# Hammerhead_-_LPC4337_MCU_R1_1.net
KiCad netlist of a schematic drawn in Altium Designer
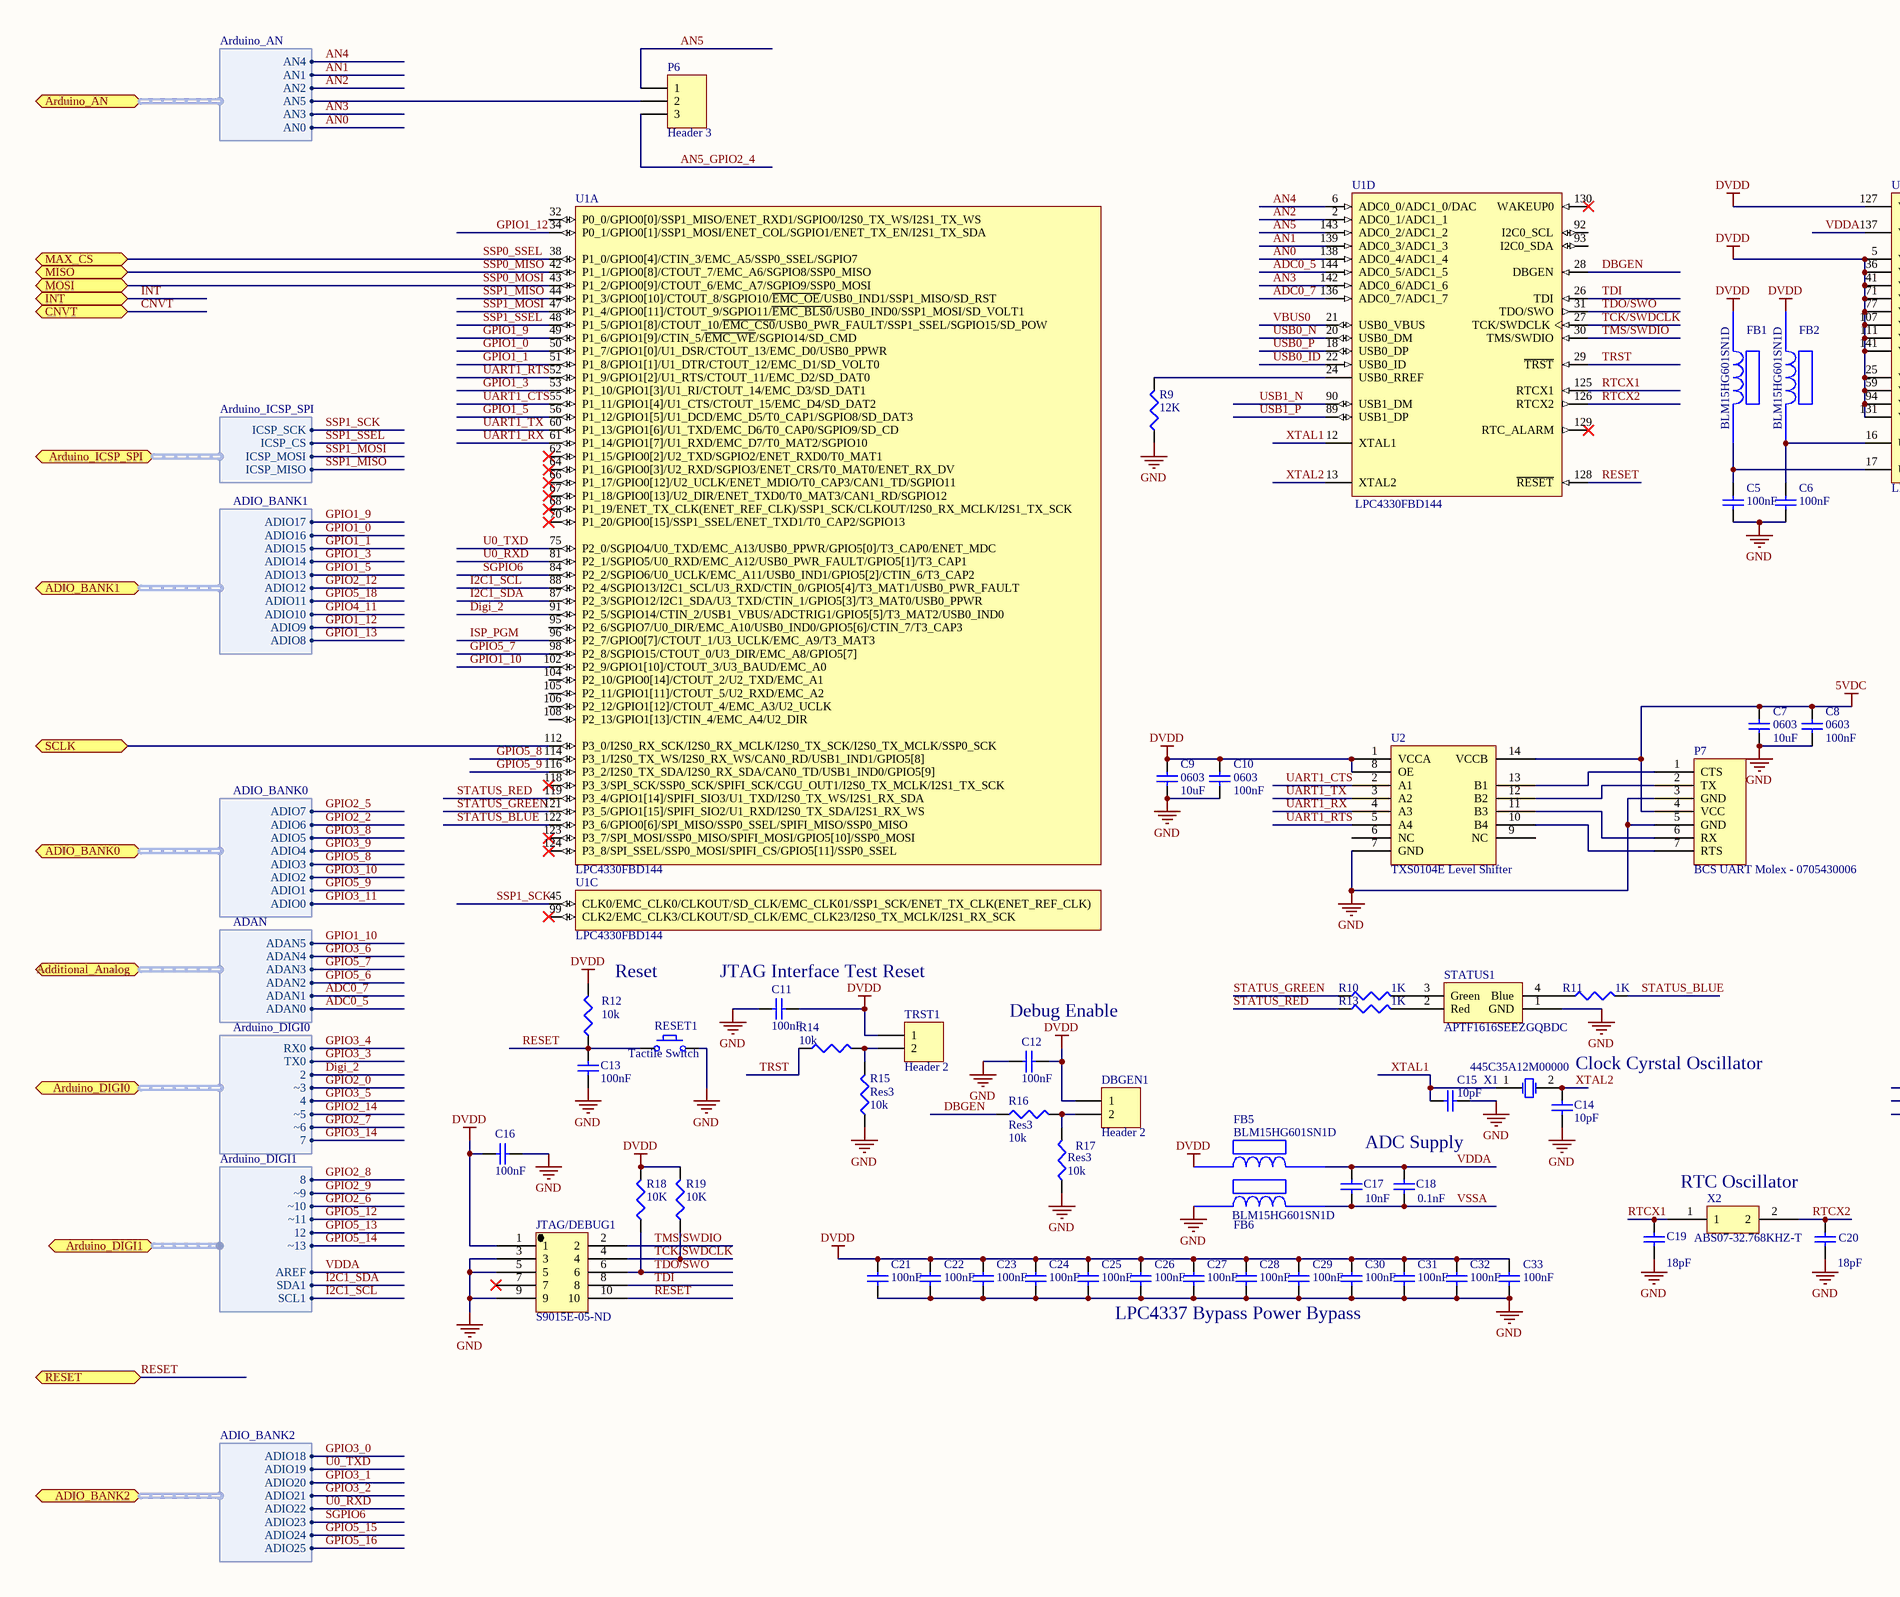
[diagram p0: Hammerhead - LPC4337 MCU R1.1.SchDoc, left]
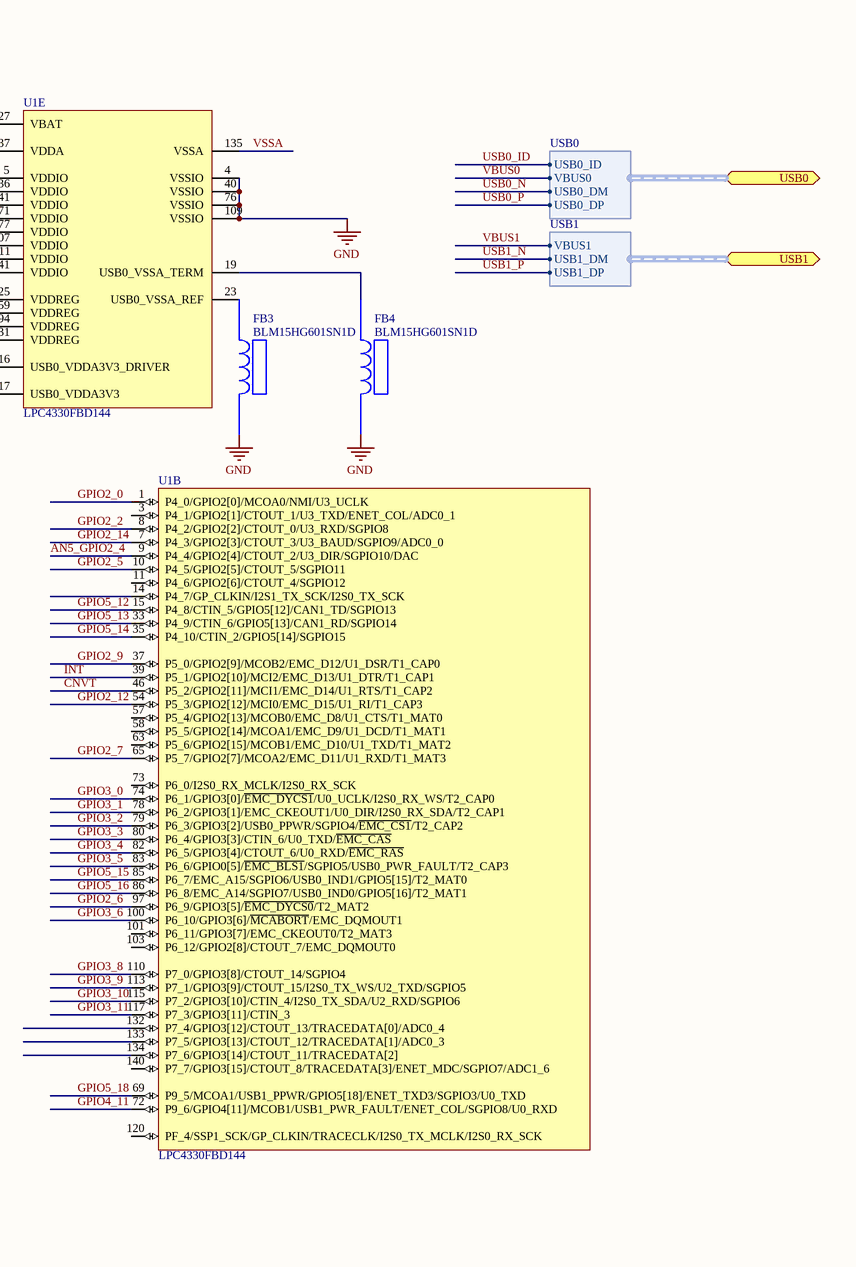
[diagram p1: Hammerhead - LPC4337 MCU R1.1.SchDoc, right]

(export (version "E")
  (design (tool "Eeschema 10.0.6"))
  (components
    (comp (ref "C5")
      (value "100nF")
      (footprint "1608[0603]")
      (description "Capacitor (Semiconductor SIM Model)")
      (fields (field (name "Comment") "Cap Semi") (field (name "PUBLISHER") "Altium Limited"))
      (libsource (lib "Miscellaneous Devices") (part "Cap Semi"))
    )
    (comp (ref "C6")
      (value "100nF")
      (footprint "1608[0603]")
      (description "Capacitor (Semiconductor SIM Model)")
      (fields (field (name "Comment") "Cap Semi") (field (name "PUBLISHER") "Altium Limited"))
      (libsource (lib "Miscellaneous Devices") (part "Cap Semi"))
    )
    (comp (ref "C7")
      (value "0603")
      (footprint "1608[0603]")
      (description "Capacitor (Semiconductor SIM Model)")
      (fields (field (name "ALTIUM_VALUE") "10uF") (field (name "PUBLISHER") "Altium Limited"))
      (libsource (lib "Miscellaneous Devices") (part "Cap Semi"))
    )
    (comp (ref "C8")
      (value "0603")
      (footprint "1608[0603]")
      (description "Capacitor (Semiconductor SIM Model)")
      (fields (field (name "ALTIUM_VALUE") "100nF") (field (name "PUBLISHER") "Altium Limited"))
      (libsource (lib "Miscellaneous Devices") (part "Cap Semi"))
    )
    (comp (ref "C9")
      (value "0603")
      (footprint "1608[0603]")
      (description "Capacitor (Semiconductor SIM Model)")
      (fields (field (name "ALTIUM_VALUE") "10uF") (field (name "PUBLISHER") "Altium Limited"))
      (libsource (lib "Miscellaneous Devices") (part "Cap Semi"))
    )
    (comp (ref "C10")
      (value "0603")
      (footprint "1608[0603]")
      (description "Capacitor (Semiconductor SIM Model)")
      (fields (field (name "ALTIUM_VALUE") "100nF") (field (name "PUBLISHER") "Altium Limited"))
      (libsource (lib "Miscellaneous Devices") (part "Cap Semi"))
    )
    (comp (ref "C11")
      (value "100nF")
      (footprint "1608[0603]")
      (description "Capacitor (Semiconductor SIM Model)")
      (fields (field (name "Comment") "Cap Semi") (field (name "PUBLISHER") "Altium Limited"))
      (libsource (lib "Miscellaneous Devices") (part "Cap Semi"))
    )
    (comp (ref "C12")
      (value "100nF")
      (footprint "1608[0603]")
      (description "Capacitor (Semiconductor SIM Model)")
      (fields (field (name "Comment") "Cap Semi") (field (name "PUBLISHER") "Altium Limited"))
      (libsource (lib "Miscellaneous Devices") (part "Cap Semi"))
    )
    (comp (ref "C13")
      (value "100nF")
      (footprint "1608[0603]")
      (description "Capacitor (Semiconductor SIM Model)")
      (fields (field (name "Comment") "Cap Semi") (field (name "PUBLISHER") "Altium Limited"))
      (libsource (lib "Miscellaneous Devices") (part "Cap Semi"))
    )
    (comp (ref "C14")
      (value "10pF")
      (footprint "1608[0603]")
      (description "Capacitor (Semiconductor SIM Model)")
      (fields (field (name "Comment") "Cap Semi") (field (name "PUBLISHER") "Altium Limited"))
      (libsource (lib "Miscellaneous Devices") (part "Cap Semi"))
    )
    (comp (ref "C15")
      (value "10pF")
      (footprint "1608[0603]")
      (description "Capacitor (Semiconductor SIM Model)")
      (fields (field (name "Comment") "Cap Semi") (field (name "PUBLISHER") "Altium Limited"))
      (libsource (lib "Miscellaneous Devices") (part "Cap Semi"))
    )
    (comp (ref "C16")
      (value "100nF")
      (footprint "1608[0603]")
      (description "Capacitor (Semiconductor SIM Model)")
      (fields (field (name "Comment") "Cap Semi") (field (name "PUBLISHER") "Altium Limited"))
      (libsource (lib "Miscellaneous Devices") (part "Cap Semi"))
    )
    (comp (ref "C17")
      (value "10nF")
      (footprint "1608[0603]")
      (description "Capacitor (Semiconductor SIM Model)")
      (fields (field (name "Comment") "Cap Semi") (field (name "PUBLISHER") "Altium Limited"))
      (libsource (lib "Miscellaneous Devices") (part "Cap Semi"))
    )
    (comp (ref "C18")
      (value "0.1nF")
      (footprint "1608[0603]")
      (description "Capacitor (Semiconductor SIM Model)")
      (fields (field (name "Comment") "Cap Semi") (field (name "PUBLISHER") "Altium Limited"))
      (libsource (lib "Miscellaneous Devices") (part "Cap Semi"))
    )
    (comp (ref "C19")
      (value "18pF")
      (footprint "1608[0603]")
      (description "Capacitor (Semiconductor SIM Model)")
      (fields (field (name "Comment") "Cap Semi") (field (name "PUBLISHER") "Altium Limited"))
      (libsource (lib "Miscellaneous Devices") (part "Cap Semi"))
    )
    (comp (ref "C20")
      (value "18pF")
      (footprint "1608[0603]")
      (description "Capacitor (Semiconductor SIM Model)")
      (fields (field (name "Comment") "Cap Semi") (field (name "PUBLISHER") "Altium Limited"))
      (libsource (lib "Miscellaneous Devices") (part "Cap Semi"))
    )
    (comp (ref "C21")
      (value "100nF")
      (footprint "1608[0603]")
      (description "Capacitor (Semiconductor SIM Model)")
      (fields (field (name "Comment") "Cap Semi") (field (name "PUBLISHER") "Altium Limited"))
      (libsource (lib "Miscellaneous Devices") (part "Cap Semi"))
    )
    (comp (ref "C22")
      (value "100nF")
      (footprint "1608[0603]")
      (description "Capacitor (Semiconductor SIM Model)")
      (fields (field (name "Comment") "Cap Semi") (field (name "PUBLISHER") "Altium Limited"))
      (libsource (lib "Miscellaneous Devices") (part "Cap Semi"))
    )
    (comp (ref "C23")
      (value "100nF")
      (footprint "1608[0603]")
      (description "Capacitor (Semiconductor SIM Model)")
      (fields (field (name "Comment") "Cap Semi") (field (name "PUBLISHER") "Altium Limited"))
      (libsource (lib "Miscellaneous Devices") (part "Cap Semi"))
    )
    (comp (ref "C24")
      (value "100nF")
      (footprint "1608[0603]")
      (description "Capacitor (Semiconductor SIM Model)")
      (fields (field (name "Comment") "Cap Semi") (field (name "PUBLISHER") "Altium Limited"))
      (libsource (lib "Miscellaneous Devices") (part "Cap Semi"))
    )
    (comp (ref "C25")
      (value "100nF")
      (footprint "1608[0603]")
      (description "Capacitor (Semiconductor SIM Model)")
      (fields (field (name "Comment") "Cap Semi") (field (name "PUBLISHER") "Altium Limited"))
      (libsource (lib "Miscellaneous Devices") (part "Cap Semi"))
    )
    (comp (ref "C26")
      (value "100nF")
      (footprint "1608[0603]")
      (description "Capacitor (Semiconductor SIM Model)")
      (fields (field (name "Comment") "Cap Semi") (field (name "PUBLISHER") "Altium Limited"))
      (libsource (lib "Miscellaneous Devices") (part "Cap Semi"))
    )
    (comp (ref "C27")
      (value "100nF")
      (footprint "1608[0603]")
      (description "Capacitor (Semiconductor SIM Model)")
      (fields (field (name "Comment") "Cap Semi") (field (name "PUBLISHER") "Altium Limited"))
      (libsource (lib "Miscellaneous Devices") (part "Cap Semi"))
    )
    (comp (ref "C28")
      (value "100nF")
      (footprint "1608[0603]")
      (description "Capacitor (Semiconductor SIM Model)")
      (fields (field (name "Comment") "Cap Semi") (field (name "PUBLISHER") "Altium Limited"))
      (libsource (lib "Miscellaneous Devices") (part "Cap Semi"))
    )
    (comp (ref "C29")
      (value "100nF")
      (footprint "1608[0603]")
      (description "Capacitor (Semiconductor SIM Model)")
      (fields (field (name "Comment") "Cap Semi") (field (name "PUBLISHER") "Altium Limited"))
      (libsource (lib "Miscellaneous Devices") (part "Cap Semi"))
    )
    (comp (ref "C30")
      (value "100nF")
      (footprint "1608[0603]")
      (description "Capacitor (Semiconductor SIM Model)")
      (fields (field (name "Comment") "Cap Semi") (field (name "PUBLISHER") "Altium Limited"))
      (libsource (lib "Miscellaneous Devices") (part "Cap Semi"))
    )
    (comp (ref "C31")
      (value "100nF")
      (footprint "1608[0603]")
      (description "Capacitor (Semiconductor SIM Model)")
      (fields (field (name "Comment") "Cap Semi") (field (name "PUBLISHER") "Altium Limited"))
      (libsource (lib "Miscellaneous Devices") (part "Cap Semi"))
    )
    (comp (ref "C32")
      (value "100nF")
      (footprint "1608[0603]")
      (description "Capacitor (Semiconductor SIM Model)")
      (fields (field (name "Comment") "Cap Semi") (field (name "PUBLISHER") "Altium Limited"))
      (libsource (lib "Miscellaneous Devices") (part "Cap Semi"))
    )
    (comp (ref "C33")
      (value "100nF")
      (footprint "1608[0603]")
      (description "Capacitor (Semiconductor SIM Model)")
      (fields (field (name "Comment") "Cap Semi") (field (name "PUBLISHER") "Altium Limited"))
      (libsource (lib "Miscellaneous Devices") (part "Cap Semi"))
    )
    (comp (ref "DBGEN1")
      (value "Header 2")
      (footprint "HDR1X2")
      (description "Header, 2-Pin")
      (fields (field (name "PUBLISHER") "Altium Limited"))
      (libsource (lib "Miscellaneous Connectors") (part "Header 2"))
    )
    (comp (ref "FB1")
      (value "BLM15HG601SN1D")
      (footprint "BLM18PG121SN1D")
      (libsource (lib "AHD Part Library") (part "BLM15HG601SN1D"))
    )
    (comp (ref "FB2")
      (value "BLM15HG601SN1D")
      (footprint "BLM18PG121SN1D")
      (libsource (lib "AHD Part Library") (part "BLM15HG601SN1D"))
    )
    (comp (ref "FB3")
      (value "BLM15HG601SN1D")
      (footprint "BLM18PG121SN1D")
      (libsource (lib "AHD Part Library") (part "BLM15HG601SN1D"))
    )
    (comp (ref "FB4")
      (value "BLM15HG601SN1D")
      (footprint "BLM18PG121SN1D")
      (libsource (lib "AHD Part Library") (part "BLM15HG601SN1D"))
    )
    (comp (ref "FB5")
      (value "BLM15HG601SN1D")
      (footprint "BLM18PG121SN1D")
      (libsource (lib "AHD Part Library") (part "BLM15HG601SN1D"))
    )
    (comp (ref "FB6")
      (value "BLM15HG601SN1D")
      (footprint "BLM18PG121SN1D")
      (libsource (lib "AHD Part Library") (part "BLM15HG601SN1D"))
    )
    (comp (ref "JTAG/DEBUG1")
      (value "S9015E-05-ND")
      (footprint "S9015E-05-ND")
      (libsource (lib "AHD Part Library") (part "S9015E-05-ND"))
    )
    (comp (ref "P6")
      (value "Header 3")
      (footprint "HDR1X3")
      (description "Header, 3-Pin")
      (fields (field (name "PUBLISHER") "Altium Limited"))
      (libsource (lib "Miscellaneous Connectors") (part "Header 3"))
    )
    (comp (ref "P7")
      (value "BCS UART Molex - 0705430006")
      (footprint "BCS Serial Port - Molex")
      (description "BCS UART Port Molex")
      (libsource (lib "SunIO Schematic Symbol Lib") (part "BCS Serial Port - Molex"))
    )
    (comp (ref "R9")
      (value "12K")
      (footprint "J1-0603")
      (description "Resistor")
      (fields (field (name "Comment") "Res3") (field (name "PUBLISHER") "Altium Limited"))
      (libsource (lib "Miscellaneous Devices") (part "Res3"))
    )
    (comp (ref "R10")
      (value "1K")
      (footprint "J1-0603")
      (description "Resistor")
      (fields (field (name "Comment") "Res3") (field (name "PUBLISHER") "Altium Limited"))
      (libsource (lib "Miscellaneous Devices") (part "Res3"))
    )
    (comp (ref "R11")
      (value "1K")
      (footprint "J1-0603")
      (description "Resistor")
      (fields (field (name "Comment") "Res3") (field (name "PUBLISHER") "Altium Limited"))
      (libsource (lib "Miscellaneous Devices") (part "Res3"))
    )
    (comp (ref "R12")
      (value "10k")
      (footprint "J1-0603")
      (description "Resistor")
      (fields (field (name "Comment") "Res3") (field (name "PUBLISHER") "Altium Limited"))
      (libsource (lib "Miscellaneous Devices") (part "Res3"))
    )
    (comp (ref "R13")
      (value "1K")
      (footprint "J1-0603")
      (description "Resistor")
      (fields (field (name "Comment") "Res3") (field (name "PUBLISHER") "Altium Limited"))
      (libsource (lib "Miscellaneous Devices") (part "Res3"))
    )
    (comp (ref "R14")
      (value "10k")
      (footprint "J1-0603")
      (description "Resistor")
      (fields (field (name "Comment") "Res3") (field (name "PUBLISHER") "Altium Limited"))
      (libsource (lib "Miscellaneous Devices") (part "Res3"))
    )
    (comp (ref "R15")
      (value "Res3")
      (footprint "J1-0603")
      (description "Resistor")
      (fields (field (name "ALTIUM_VALUE") "10k") (field (name "PUBLISHER") "Altium Limited"))
      (libsource (lib "Miscellaneous Devices") (part "Res3"))
    )
    (comp (ref "R16")
      (value "Res3")
      (footprint "J1-0603")
      (description "Resistor")
      (fields (field (name "ALTIUM_VALUE") "10k") (field (name "PUBLISHER") "Altium Limited"))
      (libsource (lib "Miscellaneous Devices") (part "Res3"))
    )
    (comp (ref "R17")
      (value "Res3")
      (footprint "J1-0603")
      (description "Resistor")
      (fields (field (name "ALTIUM_VALUE") "10k") (field (name "PUBLISHER") "Altium Limited"))
      (libsource (lib "Miscellaneous Devices") (part "Res3"))
    )
    (comp (ref "R18")
      (value "10K")
      (footprint "J1-0603")
      (description "Resistor")
      (fields (field (name "Comment") "Res3") (field (name "PUBLISHER") "Altium Limited"))
      (libsource (lib "Miscellaneous Devices") (part "Res3"))
    )
    (comp (ref "R19")
      (value "10K")
      (footprint "J1-0603")
      (description "Resistor")
      (fields (field (name "Comment") "Res3") (field (name "PUBLISHER") "Altium Limited"))
      (libsource (lib "Miscellaneous Devices") (part "Res3"))
    )
    (comp (ref "RESET1")
      (value "Tactile Switch")
      (footprint "TL3301")
      (libsource (lib "Adams Altium Library") (part "Tactile Switch"))
    )
    (comp (ref "STATUS1")
      (value "APTF1616SEEZGQBDC")
      (footprint "RGB LED APTF1616SEEZGQBDC")
      (description "RGB LED")
      (libsource (lib "Adams Altium Library") (part "RGB LED APTF1616SEEZGQBDC"))
    )
    (comp (ref "TRST1")
      (value "Header 2")
      (footprint "HDR1X2")
      (description "Header, 2-Pin")
      (fields (field (name "PUBLISHER") "Altium Limited"))
      (libsource (lib "Miscellaneous Connectors") (part "Header 2"))
    )
    (comp (ref "U1")
      (value "LPC4330FBD144")
      (footprint "SOT486-1_V")
      (libsource (lib "NXP Semiconductors Cortex-M4") (part "LPC4330FBD144"))
    )
    (comp (ref "U2")
      (value "TXS0104E Level Shifter")
      (footprint "RGY  (S-PVQFN-N14)")
      (description "TXS0104E - Bidriectional Opendrain/pushpull level shift")
      (libsource (lib "SunIO Schematic Symbol Lib") (part "TXS0104E"))
    )
    (comp (ref "X1")
      (value "445C35A12M00000")
      (footprint "445C35A12M00000")
      (description "Crystal Oscillator")
      (fields (field (name "PUBLISHER") "Altium Limited"))
      (libsource (lib "Miscellaneous Devices") (part "XTAL"))
    )
    (comp (ref "X2")
      (value "ABS07-32.768KHZ-T")
      (footprint "ABS07-32.768KHZ-T")
      (description "ABS07-32.768KHZ-T RTC Crystal Oscillator")
      (libsource (lib "AHD Part Library") (part "ABS07-32.768KHZ-T"))
    )
  )
  (nets
    (net (code "11") (name "/ADC0_5") (class "Default")
      (node (ref "U1") (pin "144") (pinfunction "ADC0_5/ADC1_5_144") (pintype "input"))
    )
    (net (code "12") (name "/ADC0_7") (class "Default")
      (node (ref "U1") (pin "136") (pinfunction "ADC0_7/ADC1_7_136") (pintype "input"))
    )
    (net (code "13") (name "/AN0") (class "Default")
      (node (ref "U1") (pin "138") (pinfunction "ADC0_4/ADC1_4_138") (pintype "input"))
    )
    (net (code "14") (name "/AN1") (class "Default")
      (node (ref "U1") (pin "139") (pinfunction "ADC0_3/ADC1_3_139") (pintype "input"))
    )
    (net (code "15") (name "/AN2") (class "Default")
      (node (ref "U1") (pin "2") (pinfunction "ADC0_1/ADC1_1_2") (pintype "input"))
    )
    (net (code "16") (name "/AN3") (class "Default")
      (node (ref "U1") (pin "142") (pinfunction "ADC0_6/ADC1_6_142") (pintype "input"))
    )
    (net (code "17") (name "/AN4") (class "Default")
      (node (ref "U1") (pin "6") (pinfunction "ADC0_0/ADC1_0/DAC_6") (pintype "input"))
    )
    (net (code "18") (name "/AN5") (class "Default")
      (node (ref "P6") (pin "1") (pinfunction "1_1") (pintype "passive"))
      (node (ref "U1") (pin "143") (pinfunction "ADC0_2/ADC1_2_143") (pintype "input"))
    )
    (net (code "19") (name "/AN5_GPIO2_4") (class "Default")
      (node (ref "P6") (pin "3") (pinfunction "3_3") (pintype "passive"))
      (node (ref "U1") (pin "9") (pinfunction "P4_4/GPIO2[4]/CTOUT_2/U3_DIR/SGPIO10/DAC_9") (pintype "bidirectional"))
    )
    (net (code "20") (name "/CNVT") (class "Default")
      (node (ref "U1") (pin "46") (pinfunction "P5_2/GPIO2[11]/MCI1/EMC_D14/U1_RTS/T1_CAP2_46") (pintype "bidirectional"))
    )
    (net (code "21") (name "/DBGEN") (class "Default")
      (node (ref "R16") (pin "1") (pinfunction "1_1") (pintype "passive"))
      (node (ref "U1") (pin "28") (pinfunction "DBGEN_28") (pintype "input"))
    )
    (net (code "22") (name "/Digi_2") (class "Default")
      (node (ref "U1") (pin "91") (pinfunction "P2_5/SGPIO14/CTIN_2/USB1_VBUS/ADCTRIG1/GPIO5[5]/T3_MAT2/USB0_IND0_91") (pintype "bidirectional"))
    )
    (net (code "23") (name "/GPIO1_0") (class "Default")
      (node (ref "U1") (pin "50") (pinfunction "P1_7/GPIO1[0]/U1_DSR/CTOUT_13/EMC_D0/USB0_PPWR_50") (pintype "bidirectional"))
    )
    (net (code "24") (name "/GPIO1_1") (class "Default")
      (node (ref "U1") (pin "51") (pinfunction "P1_8/GPIO1[1]/U1_DTR/CTOUT_12/EMC_D1/SD_VOLT0_51") (pintype "bidirectional"))
    )
    (net (code "25") (name "/GPIO1_3") (class "Default")
      (node (ref "U1") (pin "53") (pinfunction "P1_10/GPIO1[3]/U1_RI/CTOUT_14/EMC_D3/SD_DAT1_53") (pintype "bidirectional"))
    )
    (net (code "26") (name "/GPIO1_5") (class "Default")
      (node (ref "U1") (pin "56") (pinfunction "P1_12/GPIO1[5]/U1_DCD/EMC_D5/T0_CAP1/SGPIO8/SD_DAT3_56") (pintype "bidirectional"))
    )
    (net (code "27") (name "/GPIO1_9") (class "Default")
      (node (ref "U1") (pin "49") (pinfunction "P1_6/GPIO1[9]/CTIN_5/~{EMC_WE}/SGPIO14/SD_CMD_49") (pintype "bidirectional"))
    )
    (net (code "28") (name "/GPIO1_10") (class "Default")
      (node (ref "U1") (pin "102") (pinfunction "P2_9/GPIO1[10]/CTOUT_3/U3_BAUD/EMC_A0_102") (pintype "bidirectional"))
    )
    (net (code "29") (name "/GPIO1_12") (class "Default")
      (node (ref "U1") (pin "34") (pinfunction "P0_1/GPIO0[1]/SSP1_MOSI/ENET_COL/SGPIO1/ENET_TX_EN/I2S1_TX_SDA_34") (pintype "bidirectional"))
    )
    (net (code "31") (name "/GPIO2_0") (class "Default")
      (node (ref "U1") (pin "1") (pinfunction "P4_0/GPIO2[0]/MCOA0/NMI/U3_UCLK_1") (pintype "bidirectional"))
    )
    (net (code "32") (name "/GPIO2_2") (class "Default")
      (node (ref "U1") (pin "8") (pinfunction "P4_2/GPIO2[2]/CTOUT_0/U3_RXD/SGPIO8_8") (pintype "bidirectional"))
    )
    (net (code "33") (name "/GPIO2_5") (class "Default")
      (node (ref "U1") (pin "10") (pinfunction "P4_5/GPIO2[5]/CTOUT_5/SGPIO11_10") (pintype "bidirectional"))
    )
    (net (code "34") (name "/GPIO2_6") (class "Default")
      (node (ref "U1") (pin "97") (pinfunction "P6_9/GPIO3[5]/~{EMC_DYCS0}/T2_MAT2_97") (pintype "bidirectional"))
    )
    (net (code "35") (name "/GPIO2_7") (class "Default")
      (node (ref "U1") (pin "65") (pinfunction "P5_7/GPIO2[7]/MCOA2/EMC_D11/U1_RXD/T1_MAT3_65") (pintype "bidirectional"))
    )
    (net (code "37") (name "/GPIO2_9") (class "Default")
      (node (ref "U1") (pin "37") (pinfunction "P5_0/GPIO2[9]/MCOB2/EMC_D12/U1_DSR/T1_CAP0_37") (pintype "bidirectional"))
    )
    (net (code "38") (name "/GPIO2_12") (class "Default")
      (node (ref "U1") (pin "54") (pinfunction "P5_3/GPIO2[12]/MCI0/EMC_D15/U1_RI/T1_CAP3_54") (pintype "bidirectional"))
    )
    (net (code "39") (name "/GPIO2_14") (class "Default")
      (node (ref "U1") (pin "7") (pinfunction "P4_3/GPIO2[3]/CTOUT_3/U3_BAUD/SGPIO9/ADC0_0_7") (pintype "bidirectional"))
    )
    (net (code "40") (name "/GPIO3_0") (class "Default")
      (node (ref "U1") (pin "74") (pinfunction "P6_1/GPIO3[0]/~{EMC_DYCS1}/U0_UCLK/I2S0_RX_WS/T2_CAP0_74") (pintype "bidirectional"))
    )
    (net (code "41") (name "/GPIO3_1") (class "Default")
      (node (ref "U1") (pin "78") (pinfunction "P6_2/GPIO3[1]/EMC_CKEOUT1/U0_DIR/I2S0_RX_SDA/T2_CAP1_78") (pintype "bidirectional"))
    )
    (net (code "42") (name "/GPIO3_2") (class "Default")
      (node (ref "U1") (pin "79") (pinfunction "P6_3/GPIO3[2]/USB0_PPWR/SGPIO4/~{EMC_CS1}/T2_CAP2_79") (pintype "bidirectional"))
    )
    (net (code "43") (name "/GPIO3_3") (class "Default")
      (node (ref "U1") (pin "80") (pinfunction "P6_4/GPIO3[3]/CTIN_6/U0_TXD/~{EMC_CAS}_80") (pintype "bidirectional"))
    )
    (net (code "44") (name "/GPIO3_4") (class "Default")
      (node (ref "U1") (pin "82") (pinfunction "P6_5/GPIO3[4]/CTOUT_6/U0_RXD/~{EMC_RAS}_82") (pintype "bidirectional"))
    )
    (net (code "45") (name "/GPIO3_5") (class "Default")
      (node (ref "U1") (pin "83") (pinfunction "P6_6/GPIO0[5]/~{EMC_BLS1}/SGPIO5/USB0_PWR_FAULT/T2_CAP3_83") (pintype "bidirectional"))
    )
    (net (code "46") (name "/GPIO3_6") (class "Default")
      (node (ref "U1") (pin "100") (pinfunction "P6_10/GPIO3[6]/~{MCABORT}/EMC_DQMOUT1_100") (pintype "bidirectional"))
    )
    (net (code "47") (name "/GPIO3_8") (class "Default")
      (node (ref "U1") (pin "110") (pinfunction "P7_0/GPIO3[8]/CTOUT_14/SGPIO4_110") (pintype "bidirectional"))
    )
    (net (code "48") (name "/GPIO3_9") (class "Default")
      (node (ref "U1") (pin "113") (pinfunction "P7_1/GPIO3[9]/CTOUT_15/I2S0_TX_WS/U2_TXD/SGPIO5_113") (pintype "bidirectional"))
    )
    (net (code "49") (name "/GPIO3_10") (class "Default")
      (node (ref "U1") (pin "115") (pinfunction "P7_2/GPIO3[10]/CTIN_4/I2S0_TX_SDA/U2_RXD/SGPIO6_115") (pintype "bidirectional"))
    )
    (net (code "50") (name "/GPIO3_11") (class "Default")
      (node (ref "U1") (pin "117") (pinfunction "P7_3/GPIO3[11]/CTIN_3_117") (pintype "bidirectional"))
    )
    (net (code "52") (name "/GPIO4_11") (class "Default")
      (node (ref "U1") (pin "72") (pinfunction "P9_6/GPIO4[11]/MCOB1/USB1_PWR_FAULT/ENET_COL/SGPIO8/U0_RXD_72") (pintype "bidirectional"))
    )
    (net (code "54") (name "/GPIO5_7") (class "Default")
      (node (ref "U1") (pin "98") (pinfunction "P2_8/SGPIO15/CTOUT_0/U3_DIR/EMC_A8/GPIO5[7]_98") (pintype "bidirectional"))
    )
    (net (code "55") (name "/GPIO5_8") (class "Default")
      (node (ref "U1") (pin "114") (pinfunction "P3_1/I2S0_TX_WS/I2S0_RX_WS/CAN0_RD/USB1_IND1/GPIO5[8]_114") (pintype "bidirectional"))
    )
    (net (code "56") (name "/GPIO5_9") (class "Default")
      (node (ref "U1") (pin "116") (pinfunction "P3_2/I2S0_TX_SDA/I2S0_RX_SDA/CAN0_TD/USB1_IND0/GPIO5[9]_116") (pintype "bidirectional"))
    )
    (net (code "57") (name "/GPIO5_12") (class "Default")
      (node (ref "U1") (pin "15") (pinfunction "P4_8/CTIN_5/GPIO5[12]/CAN1_TD/SGPIO13_15") (pintype "bidirectional"))
    )
    (net (code "58") (name "/GPIO5_13") (class "Default")
      (node (ref "U1") (pin "33") (pinfunction "P4_9/CTIN_6/GPIO5[13]/CAN1_RD/SGPIO14_33") (pintype "bidirectional"))
    )
    (net (code "59") (name "/GPIO5_14") (class "Default")
      (node (ref "U1") (pin "35") (pinfunction "P4_10/CTIN_2/GPIO5[14]/SGPIO15_35") (pintype "bidirectional"))
    )
    (net (code "60") (name "/GPIO5_15") (class "Default")
      (node (ref "U1") (pin "85") (pinfunction "P6_7/EMC_A15/SGPIO6/USB0_IND1/GPIO5[15]/T2_MAT0_85") (pintype "bidirectional"))
    )
    (net (code "61") (name "/GPIO5_16") (class "Default")
      (node (ref "U1") (pin "86") (pinfunction "P6_8/EMC_A14/SGPIO7/USB0_IND0/GPIO5[16]/T2_MAT1_86") (pintype "bidirectional"))
    )
    (net (code "62") (name "/GPIO5_18") (class "Default")
      (node (ref "U1") (pin "69") (pinfunction "P9_5/MCOA1/USB1_PPWR/GPIO5[18]/ENET_TXD3/SGPIO3/U0_TXD_69") (pintype "bidirectional"))
    )
    (net (code "63") (name "/I2C1_SCL") (class "Default")
      (node (ref "U1") (pin "88") (pinfunction "P2_4/SGPIO13/I2C1_SCL/U3_RXD/CTIN_0/GPIO5[4]/T3_MAT1/USB0_PWR_FAULT_88") (pintype "bidirectional"))
    )
    (net (code "64") (name "/I2C1_SDA") (class "Default")
      (node (ref "U1") (pin "87") (pinfunction "P2_3/SGPIO12/I2C1_SDA/U3_TXD/CTIN_1/GPIO5[3]/T3_MAT0/USB0_PPWR_87") (pintype "bidirectional"))
    )
    (net (code "65") (name "/INT") (class "Default")
      (node (ref "U1") (pin "39") (pinfunction "P5_1/GPIO2[10]/MCI2/EMC_D13/U1_DTR/T1_CAP1_39") (pintype "bidirectional"))
    )
    (net (code "66") (name "/ISP_PGM") (class "Default")
      (node (ref "U1") (pin "96") (pinfunction "P2_7/GPIO0[7]/CTOUT_1/U3_UCLK/EMC_A9/T3_MAT3_96") (pintype "bidirectional"))
    )
    (net (code "67") (name "/RESET") (class "Default")
      (node (ref "C13") (pin "2") (pinfunction "2_2") (pintype "passive"))
      (node (ref "JTAG/DEBUG1") (pin "10") (pinfunction "10_10") (pintype "passive"))
      (node (ref "R12") (pin "1") (pinfunction "1_1") (pintype "passive"))
      (node (ref "RESET1") (pin "1") (pintype "passive"))
      (node (ref "U1") (pin "128") (pinfunction "~{RESET}_128") (pintype "input"))
    )
    (net (code "68") (name "/RTCX1") (class "Default")
      (node (ref "C19") (pin "2") (pinfunction "2_2") (pintype "passive"))
      (node (ref "U1") (pin "125") (pinfunction "RTCX1_125") (pintype "input"))
      (node (ref "X2") (pin "1") (pinfunction "1_1") (pintype "passive"))
    )
    (net (code "69") (name "/RTCX2") (class "Default")
      (node (ref "C20") (pin "2") (pinfunction "2_2") (pintype "passive"))
      (node (ref "U1") (pin "126") (pinfunction "RTCX2_126") (pintype "output"))
      (node (ref "X2") (pin "2") (pinfunction "2_2") (pintype "passive"))
    )
    (net (code "70") (name "/SCLK") (class "Default")
      (node (ref "U1") (pin "112") (pinfunction "P3_0/I2S0_RX_SCK/I2S0_RX_MCLK/I2S0_TX_SCK/I2S0_TX_MCLK/SSP0_SCK_112") (pintype "bidirectional"))
    )
    (net (code "71") (name "/SGPIO6") (class "Default")
      (node (ref "U1") (pin "84") (pinfunction "P2_2/SGPIO6/U0_UCLK/EMC_A11/USB0_IND1/GPIO5[2]/CTIN_6/T3_CAP2_84") (pintype "bidirectional"))
    )
    (net (code "72") (name "/SSP0_MISO") (class "Default")
      (node (ref "U1") (pin "42") (pinfunction "P1_1/GPIO0[8]/CTOUT_7/EMC_A6/SGPIO8/SSP0_MISO_42") (pintype "bidirectional"))
    )
    (net (code "73") (name "/SSP0_MOSI") (class "Default")
      (node (ref "U1") (pin "43") (pinfunction "P1_2/GPIO0[9]/CTOUT_6/EMC_A7/SGPIO9/SSP0_MOSI_43") (pintype "bidirectional"))
    )
    (net (code "74") (name "/SSP0_SSEL") (class "Default")
      (node (ref "U1") (pin "38") (pinfunction "P1_0/GPIO0[4]/CTIN_3/EMC_A5/SSP0_SSEL/SGPIO7_38") (pintype "bidirectional"))
    )
    (net (code "75") (name "/SSP1_MISO") (class "Default")
      (node (ref "U1") (pin "44") (pinfunction "P1_3/GPIO0[10]/CTOUT_8/SGPIO10/~{EMC_OE}/USB0_IND1/SSP1_MISO/SD_RST_44") (pintype "bidirectional"))
    )
    (net (code "76") (name "/SSP1_MOSI") (class "Default")
      (node (ref "U1") (pin "47") (pinfunction "P1_4/GPIO0[11]/CTOUT_9/SGPIO11/~{EMC_BLS0}/USB0_IND0/SSP1_MOSI/SD_VOLT1_47") (pintype "bidirectional"))
    )
    (net (code "77") (name "/SSP1_SCK") (class "Default")
      (node (ref "U1") (pin "45") (pinfunction "CLK0/EMC_CLK0/CLKOUT/SD_CLK/EMC_CLK01/SSP1_SCK/ENET_TX_CLK(ENET_REF_CLK)_45") (pintype "bidirectional"))
    )
    (net (code "78") (name "/SSP1_SSEL") (class "Default")
      (node (ref "U1") (pin "48") (pinfunction "P1_5/GPIO1[8]/CTOUT_10/~{EMC_CS0}/USB0_PWR_FAULT/SSP1_SSEL/SGPIO15/SD_POW_48") (pintype "bidirectional"))
    )
    (net (code "79") (name "/STATUS_BLUE") (class "Default")
      (node (ref "R11") (pin "2") (pinfunction "2_2") (pintype "passive"))
      (node (ref "U1") (pin "122") (pinfunction "P3_6/GPIO0[6]/SPI_MISO/SSP0_SSEL/SPIFI_MISO/SSP0_MISO_122") (pintype "bidirectional"))
    )
    (net (code "80") (name "/STATUS_GREEN") (class "Default")
      (node (ref "R10") (pin "1") (pinfunction "1_1") (pintype "passive"))
      (node (ref "U1") (pin "121") (pinfunction "P3_5/GPIO1[15]/SPIFI_SIO2/U1_RXD/I2S0_TX_SDA/I2S1_RX_WS_121") (pintype "bidirectional"))
    )
    (net (code "81") (name "/STATUS_RED") (class "Default")
      (node (ref "R13") (pin "1") (pinfunction "1_1") (pintype "passive"))
      (node (ref "U1") (pin "119") (pinfunction "P3_4/GPIO1[14]/SPIFI_SIO3/U1_TXD/I2S0_TX_WS/I2S1_RX_SDA_119") (pintype "bidirectional"))
    )
    (net (code "82") (name "/TCK{slash}SWDCLK") (class "Default")
      (node (ref "JTAG/DEBUG1") (pin "4") (pinfunction "4_4") (pintype "passive"))
      (node (ref "R19") (pin "1") (pinfunction "1_1") (pintype "passive"))
      (node (ref "U1") (pin "27") (pinfunction "TCK/SWDCLK_27") (pintype "input"))
    )
    (net (code "83") (name "/TDI") (class "Default")
      (node (ref "JTAG/DEBUG1") (pin "8") (pinfunction "8_8") (pintype "passive"))
      (node (ref "U1") (pin "26") (pinfunction "TDI_26") (pintype "input"))
    )
    (net (code "84") (name "/TDO{slash}SWO") (class "Default")
      (node (ref "JTAG/DEBUG1") (pin "6") (pinfunction "6_6") (pintype "passive"))
      (node (ref "R18") (pin "1") (pinfunction "1_1") (pintype "passive"))
      (node (ref "U1") (pin "31") (pinfunction "TDO/SWO_31") (pintype "output"))
    )
    (net (code "85") (name "/TMS{slash}SWDIO") (class "Default")
      (node (ref "JTAG/DEBUG1") (pin "2") (pinfunction "2_2") (pintype "passive"))
      (node (ref "U1") (pin "30") (pinfunction "TMS/SWDIO_30") (pintype "input"))
    )
    (net (code "86") (name "/TRST") (class "Default")
      (node (ref "R14") (pin "1") (pinfunction "1_1") (pintype "passive"))
      (node (ref "U1") (pin "29") (pinfunction "~{TRST}_29") (pintype "input"))
    )
    (net (code "87") (name "/U0_RXD") (class "Default")
      (node (ref "U1") (pin "81") (pinfunction "P2_1/SGPIO5/U0_RXD/EMC_A12/USB0_PWR_FAULT/GPIO5[1]/T3_CAP1_81") (pintype "bidirectional"))
    )
    (net (code "88") (name "/U0_TXD") (class "Default")
      (node (ref "U1") (pin "75") (pinfunction "P2_0/SGPIO4/U0_TXD/EMC_A13/USB0_PPWR/GPIO5[0]/T3_CAP0/ENET_MDC_75") (pintype "bidirectional"))
    )
    (net (code "89") (name "/UART1_CTS") (class "Default")
      (node (ref "U1") (pin "55") (pinfunction "P1_11/GPIO1[4]/U1_CTS/CTOUT_15/EMC_D4/SD_DAT2_55") (pintype "bidirectional"))
      (node (ref "U2") (pin "2") (pinfunction "A1_2") (pintype "passive"))
    )
    (net (code "90") (name "/UART1_RTS") (class "Default")
      (node (ref "U1") (pin "52") (pinfunction "P1_9/GPIO1[2]/U1_RTS/CTOUT_11/EMC_D2/SD_DAT0_52") (pintype "bidirectional"))
      (node (ref "U2") (pin "5") (pinfunction "A4_5") (pintype "passive"))
    )
    (net (code "91") (name "/UART1_RX") (class "Default")
      (node (ref "U1") (pin "61") (pinfunction "P1_14/GPIO1[7]/U1_RXD/EMC_D7/T0_MAT2/SGPIO10_61") (pintype "bidirectional"))
      (node (ref "U2") (pin "4") (pinfunction "A3_4") (pintype "passive"))
    )
    (net (code "92") (name "/UART1_TX") (class "Default")
      (node (ref "U1") (pin "60") (pinfunction "P1_13/GPIO1[6]/U1_TXD/EMC_D6/T0_CAP0/SGPIO9/SD_CD_60") (pintype "bidirectional"))
      (node (ref "U2") (pin "3") (pinfunction "A2_3") (pintype "passive"))
    )
    (net (code "93") (name "/USB0_ID") (class "Default")
      (node (ref "U1") (pin "22") (pinfunction "USB0_ID_22") (pintype "input"))
    )
    (net (code "94") (name "/USB0_N") (class "Default")
      (node (ref "U1") (pin "20") (pinfunction "USB0_DM_20") (pintype "bidirectional"))
    )
    (net (code "95") (name "/USB0_P") (class "Default")
      (node (ref "U1") (pin "18") (pinfunction "USB0_DP_18") (pintype "bidirectional"))
    )
    (net (code "96") (name "/USB1_N") (class "Default")
      (node (ref "U1") (pin "90") (pinfunction "USB1_DM_90") (pintype "bidirectional"))
    )
    (net (code "97") (name "/USB1_P") (class "Default")
      (node (ref "U1") (pin "89") (pinfunction "USB1_DP_89") (pintype "bidirectional"))
    )
    (net (code "98") (name "/VBUS0") (class "Default")
      (node (ref "U1") (pin "21") (pinfunction "USB0_VBUS_21") (pintype "bidirectional"))
    )
    (net (code "100") (name "/VDDA") (class "Default")
      (node (ref "C17") (pin "2") (pinfunction "2_2") (pintype "passive"))
      (node (ref "C18") (pin "2") (pinfunction "2_2") (pintype "passive"))
      (node (ref "FB5") (pin "2") (pinfunction "2_2") (pintype "passive"))
      (node (ref "U1") (pin "137") (pinfunction "VDDA_137") (pintype "power_in"))
    )
    (net (code "101") (name "/VSSA") (class "Default")
      (node (ref "C17") (pin "1") (pinfunction "1_1") (pintype "passive"))
      (node (ref "C18") (pin "1") (pinfunction "1_1") (pintype "passive"))
      (node (ref "FB6") (pin "2") (pinfunction "2_2") (pintype "passive"))
      (node (ref "U1") (pin "135") (pinfunction "VSSA_135") (pintype "power_in"))
    )
    (net (code "102") (name "/XTAL1") (class "Default")
      (node (ref "C15") (pin "2") (pinfunction "2_2") (pintype "passive"))
      (node (ref "U1") (pin "12") (pinfunction "XTAL1_12") (pintype "passive"))
      (node (ref "X1") (pin "1") (pinfunction "OSC1_1") (pintype "passive"))
    )
    (net (code "103") (name "/XTAL2") (class "Default")
      (node (ref "C14") (pin "2") (pinfunction "2_2") (pintype "passive"))
      (node (ref "U1") (pin "13") (pinfunction "XTAL2_13") (pintype "passive"))
      (node (ref "X1") (pin "2") (pinfunction "OSC2_2") (pintype "passive"))
    )
    (net (code "114") (name "5VDC") (class "Default")
      (node (ref "C7") (pin "2") (pinfunction "2_2") (pintype "passive"))
      (node (ref "C8") (pin "2") (pinfunction "2_2") (pintype "passive"))
      (node (ref "P7") (pin "4") (pinfunction "VCC_4") (pintype "passive"))
      (node (ref "U2") (pin "14") (pinfunction "VCCB_14") (pintype "passive"))
    )
    (net (code "115") (name "DVDD") (class "Default")
      (node (ref "C10") (pin "2") (pinfunction "2_2") (pintype "passive"))
      (node (ref "C11") (pin "2") (pinfunction "2_2") (pintype "passive"))
      (node (ref "C12") (pin "2") (pinfunction "2_2") (pintype "passive"))
      (node (ref "C16") (pin "1") (pinfunction "1_1") (pintype "passive"))
      (node (ref "C21") (pin "2") (pinfunction "2_2") (pintype "passive"))
      (node (ref "C22") (pin "2") (pinfunction "2_2") (pintype "passive"))
      (node (ref "C23") (pin "2") (pinfunction "2_2") (pintype "passive"))
      (node (ref "C24") (pin "2") (pinfunction "2_2") (pintype "passive"))
      (node (ref "C25") (pin "2") (pinfunction "2_2") (pintype "passive"))
      (node (ref "C26") (pin "2") (pinfunction "2_2") (pintype "passive"))
      (node (ref "C27") (pin "2") (pinfunction "2_2") (pintype "passive"))
      (node (ref "C28") (pin "2") (pinfunction "2_2") (pintype "passive"))
      (node (ref "C29") (pin "2") (pinfunction "2_2") (pintype "passive"))
      (node (ref "C30") (pin "2") (pinfunction "2_2") (pintype "passive"))
      (node (ref "C31") (pin "2") (pinfunction "2_2") (pintype "passive"))
      (node (ref "C32") (pin "2") (pinfunction "2_2") (pintype "passive"))
      (node (ref "C33") (pin "2") (pinfunction "2_2") (pintype "passive"))
      (node (ref "C9") (pin "2") (pinfunction "2_2") (pintype "passive"))
      (node (ref "DBGEN1") (pin "1") (pinfunction "1_1") (pintype "passive"))
      (node (ref "FB1") (pin "1") (pinfunction "1_1") (pintype "passive"))
      (node (ref "FB2") (pin "1") (pinfunction "1_1") (pintype "passive"))
      (node (ref "FB5") (pin "1") (pinfunction "1_1") (pintype "passive"))
      (node (ref "JTAG/DEBUG1") (pin "1") (pinfunction "1_1") (pintype "passive"))
      (node (ref "R12") (pin "2") (pinfunction "2_2") (pintype "passive"))
      (node (ref "R18") (pin "2") (pinfunction "2_2") (pintype "passive"))
      (node (ref "R19") (pin "2") (pinfunction "2_2") (pintype "passive"))
      (node (ref "TRST1") (pin "1") (pinfunction "1_1") (pintype "passive"))
      (node (ref "U1") (pin "107") (pinfunction "VDDIO_107") (pintype "power_in"))
      (node (ref "U1") (pin "111") (pinfunction "VDDIO_111") (pintype "power_in"))
      (node (ref "U1") (pin "127") (pinfunction "VBAT_127") (pintype "power_in"))
      (node (ref "U1") (pin "131") (pinfunction "VDDREG_131") (pintype "power_in"))
      (node (ref "U1") (pin "141") (pinfunction "VDDIO_141") (pintype "power_in"))
      (node (ref "U1") (pin "25") (pinfunction "VDDREG_25") (pintype "power_in"))
      (node (ref "U1") (pin "36") (pinfunction "VDDIO_36") (pintype "power_in"))
      (node (ref "U1") (pin "41") (pinfunction "VDDIO_41") (pintype "power_in"))
      (node (ref "U1") (pin "5") (pinfunction "VDDIO_5") (pintype "power_in"))
      (node (ref "U1") (pin "59") (pinfunction "VDDREG_59") (pintype "power_in"))
      (node (ref "U1") (pin "71") (pinfunction "VDDIO_71") (pintype "power_in"))
      (node (ref "U1") (pin "77") (pinfunction "VDDIO_77") (pintype "power_in"))
      (node (ref "U1") (pin "94") (pinfunction "VDDREG_94") (pintype "power_in"))
      (node (ref "U2") (pin "1") (pinfunction "VCCA_1") (pintype "passive"))
      (node (ref "U2") (pin "8") (pinfunction "OE_8") (pintype "passive"))
    )
    (net (code "116") (name "GND") (class "Default")
      (node (ref "C10") (pin "1") (pinfunction "1_1") (pintype "passive"))
      (node (ref "C11") (pin "1") (pinfunction "1_1") (pintype "passive"))
      (node (ref "C12") (pin "1") (pinfunction "1_1") (pintype "passive"))
      (node (ref "C13") (pin "1") (pinfunction "1_1") (pintype "passive"))
      (node (ref "C14") (pin "1") (pinfunction "1_1") (pintype "passive"))
      (node (ref "C15") (pin "1") (pinfunction "1_1") (pintype "passive"))
      (node (ref "C16") (pin "2") (pinfunction "2_2") (pintype "passive"))
      (node (ref "C19") (pin "1") (pinfunction "1_1") (pintype "passive"))
      (node (ref "C20") (pin "1") (pinfunction "1_1") (pintype "passive"))
      (node (ref "C21") (pin "1") (pinfunction "1_1") (pintype "passive"))
      (node (ref "C22") (pin "1") (pinfunction "1_1") (pintype "passive"))
      (node (ref "C23") (pin "1") (pinfunction "1_1") (pintype "passive"))
      (node (ref "C24") (pin "1") (pinfunction "1_1") (pintype "passive"))
      (node (ref "C25") (pin "1") (pinfunction "1_1") (pintype "passive"))
      (node (ref "C26") (pin "1") (pinfunction "1_1") (pintype "passive"))
      (node (ref "C27") (pin "1") (pinfunction "1_1") (pintype "passive"))
      (node (ref "C28") (pin "1") (pinfunction "1_1") (pintype "passive"))
      (node (ref "C29") (pin "1") (pinfunction "1_1") (pintype "passive"))
      (node (ref "C30") (pin "1") (pinfunction "1_1") (pintype "passive"))
      (node (ref "C31") (pin "1") (pinfunction "1_1") (pintype "passive"))
      (node (ref "C32") (pin "1") (pinfunction "1_1") (pintype "passive"))
      (node (ref "C33") (pin "1") (pinfunction "1_1") (pintype "passive"))
      (node (ref "C5") (pin "1") (pinfunction "1_1") (pintype "passive"))
      (node (ref "C6") (pin "1") (pinfunction "1_1") (pintype "passive"))
      (node (ref "C7") (pin "1") (pinfunction "1_1") (pintype "passive"))
      (node (ref "C8") (pin "1") (pinfunction "1_1") (pintype "passive"))
      (node (ref "C9") (pin "1") (pinfunction "1_1") (pintype "passive"))
      (node (ref "FB3") (pin "2") (pinfunction "2_2") (pintype "passive"))
      (node (ref "FB4") (pin "2") (pinfunction "2_2") (pintype "passive"))
      (node (ref "FB6") (pin "1") (pinfunction "1_1") (pintype "passive"))
      (node (ref "JTAG/DEBUG1") (pin "3") (pinfunction "3_3") (pintype "passive"))
      (node (ref "JTAG/DEBUG1") (pin "5") (pinfunction "5_5") (pintype "passive"))
      (node (ref "JTAG/DEBUG1") (pin "9") (pinfunction "9_9") (pintype "passive"))
      (node (ref "P7") (pin "3") (pinfunction "GND_3") (pintype "passive"))
      (node (ref "P7") (pin "5") (pinfunction "GND_5") (pintype "passive"))
      (node (ref "R15") (pin "1") (pinfunction "1_1") (pintype "passive"))
      (node (ref "R17") (pin "1") (pinfunction "1_1") (pintype "passive"))
      (node (ref "R9") (pin "1") (pinfunction "1_1") (pintype "passive"))
      (node (ref "RESET1") (pin "2") (pintype "passive"))
      (node (ref "STATUS1") (pin "1") (pinfunction "GND_1") (pintype "passive"))
      (node (ref "U1") (pin "109") (pinfunction "VSSIO_109") (pintype "power_in"))
      (node (ref "U1") (pin "4") (pinfunction "VSSIO_4") (pintype "power_in"))
      (node (ref "U1") (pin "40") (pinfunction "VSSIO_40") (pintype "power_in"))
      (node (ref "U1") (pin "76") (pinfunction "VSSIO_76") (pintype "power_in"))
      (node (ref "U2") (pin "7") (pinfunction "GND_7") (pintype "passive"))
    )
    (net (code "117") (name "Net-(DBGEN1-Pad2)") (class "Default")
      (node (ref "DBGEN1") (pin "2") (pinfunction "2_2") (pintype "passive"))
      (node (ref "R16") (pin "2") (pinfunction "2_2") (pintype "passive"))
      (node (ref "R17") (pin "2") (pinfunction "2_2") (pintype "passive"))
    )
    (net (code "118") (name "Net-(P7-CTS)") (class "Default")
      (node (ref "P7") (pin "1") (pinfunction "CTS_1") (pintype "passive"))
      (node (ref "U2") (pin "13") (pinfunction "B1_13") (pintype "passive"))
    )
    (net (code "119") (name "Net-(P7-RTS)") (class "Default")
      (node (ref "P7") (pin "7") (pinfunction "RTS_7") (pintype "passive"))
      (node (ref "U2") (pin "10") (pinfunction "B4_10") (pintype "passive"))
    )
    (net (code "120") (name "Net-(P7-RX)") (class "Default")
      (node (ref "P7") (pin "6") (pinfunction "RX_6") (pintype "passive"))
      (node (ref "U2") (pin "11") (pinfunction "B3_11") (pintype "passive"))
    )
    (net (code "121") (name "Net-(P7-TX)") (class "Default")
      (node (ref "P7") (pin "2") (pinfunction "TX_2") (pintype "passive"))
      (node (ref "U2") (pin "12") (pinfunction "B2_12") (pintype "passive"))
    )
    (net (code "122") (name "Net-(R14-Pad2)") (class "Default")
      (node (ref "R14") (pin "2") (pinfunction "2_2") (pintype "passive"))
      (node (ref "R15") (pin "2") (pinfunction "2_2") (pintype "passive"))
      (node (ref "TRST1") (pin "2") (pinfunction "2_2") (pintype "passive"))
    )
    (net (code "123") (name "Net-(STATUS1-Blue)") (class "Default")
      (node (ref "R11") (pin "1") (pinfunction "1_1") (pintype "passive"))
      (node (ref "STATUS1") (pin "4") (pinfunction "Blue_4") (pintype "passive"))
    )
    (net (code "124") (name "Net-(STATUS1-Green)") (class "Default")
      (node (ref "R10") (pin "2") (pinfunction "2_2") (pintype "passive"))
      (node (ref "STATUS1") (pin "3") (pinfunction "Green_3") (pintype "passive"))
    )
    (net (code "125") (name "Net-(STATUS1-Red)") (class "Default")
      (node (ref "R13") (pin "2") (pinfunction "2_2") (pintype "passive"))
      (node (ref "STATUS1") (pin "2") (pinfunction "Red_2") (pintype "passive"))
    )
    (net (code "126") (name "Net-(U1D-USB0_RREF)") (class "Default")
      (node (ref "R9") (pin "2") (pinfunction "2_2") (pintype "passive"))
      (node (ref "U1") (pin "24") (pinfunction "USB0_RREF_24") (pintype "passive"))
    )
    (net (code "127") (name "Net-(U1E-USB0_VDDA3V3)") (class "Default")
      (node (ref "C5") (pin "2") (pinfunction "2_2") (pintype "passive"))
      (node (ref "FB1") (pin "2") (pinfunction "2_2") (pintype "passive"))
      (node (ref "U1") (pin "17") (pinfunction "USB0_VDDA3V3_17") (pintype "power_in"))
    )
    (net (code "128") (name "Net-(U1E-USB0_VDDA3V3_DRIVER)") (class "Default")
      (node (ref "C6") (pin "2") (pinfunction "2_2") (pintype "passive"))
      (node (ref "FB2") (pin "2") (pinfunction "2_2") (pintype "passive"))
      (node (ref "U1") (pin "16") (pinfunction "USB0_VDDA3V3_DRIVER_16") (pintype "power_in"))
    )
    (net (code "129") (name "Net-(U1E-USB0_VSSA_REF)") (class "Default")
      (node (ref "FB3") (pin "1") (pinfunction "1_1") (pintype "passive"))
      (node (ref "U1") (pin "23") (pinfunction "USB0_VSSA_REF_23") (pintype "power_in"))
    )
    (net (code "130") (name "Net-(U1E-USB0_VSSA_TERM)") (class "Default")
      (node (ref "FB4") (pin "1") (pinfunction "1_1") (pintype "passive"))
      (node (ref "U1") (pin "19") (pinfunction "USB0_VSSA_TERM_19") (pintype "power_in"))
    )
    (net (code "131") (name "unconnected-(JTAG/DEBUG1-Pad7)") (class "Default")
      (node (ref "JTAG/DEBUG1") (pin "7") (pinfunction "7_7") (pintype "passive+no_connect"))
    )
    (net (code "132") (name "unconnected-(P6-Pad2)") (class "Default")
      (node (ref "P6") (pin "2") (pinfunction "2_2") (pintype "passive"))
    )
    (net (code "133") (name "unconnected-(U1A-P0_0{slash}GPIO0[0]{slash}SSP1_MISO{slash}ENET_RXD1{slash}SGPIO0{slash}I2S0_TX_WS{slash}I2S1_TX_WS-Pad32)") (class "Default")
      (node (ref "U1") (pin "32") (pinfunction "P0_0/GPIO0[0]/SSP1_MISO/ENET_RXD1/SGPIO0/I2S0_TX_WS/I2S1_TX_WS_32") (pintype "bidirectional"))
    )
    (net (code "134") (name "unconnected-(U1A-P1_15{slash}GPIO0[2]{slash}U2_TXD{slash}SGPIO2{slash}ENET_RXD0{slash}T0_MAT1-Pad62)") (class "Default")
      (node (ref "U1") (pin "62") (pinfunction "P1_15/GPIO0[2]/U2_TXD/SGPIO2/ENET_RXD0/T0_MAT1_62") (pintype "bidirectional+no_connect"))
    )
    (net (code "135") (name "unconnected-(U1A-P1_16{slash}GPIO0[3]{slash}U2_RXD{slash}SGPIO3{slash}ENET_CRS{slash}T0_MAT0{slash}ENET_RX_DV-Pad64)") (class "Default")
      (node (ref "U1") (pin "64") (pinfunction "P1_16/GPIO0[3]/U2_RXD/SGPIO3/ENET_CRS/T0_MAT0/ENET_RX_DV_64") (pintype "bidirectional+no_connect"))
    )
    (net (code "136") (name "unconnected-(U1A-P1_17{slash}GPIO0[12]{slash}U2_UCLK{slash}ENET_MDIO{slash}T0_CAP3{slash}CAN1_TD{slash}SGPIO11-Pad66)") (class "Default")
      (node (ref "U1") (pin "66") (pinfunction "P1_17/GPIO0[12]/U2_UCLK/ENET_MDIO/T0_CAP3/CAN1_TD/SGPIO11_66") (pintype "bidirectional+no_connect"))
    )
    (net (code "137") (name "unconnected-(U1A-P1_18{slash}GPIO0[13]{slash}U2_DIR{slash}ENET_TXD0{slash}T0_MAT3{slash}CAN1_RD{slash}SGPIO12-Pad67)") (class "Default")
      (node (ref "U1") (pin "67") (pinfunction "P1_18/GPIO0[13]/U2_DIR/ENET_TXD0/T0_MAT3/CAN1_RD/SGPIO12_67") (pintype "bidirectional+no_connect"))
    )
    (net (code "138") (name "unconnected-(U1A-P1_19{slash}ENET_TX_CLK(ENET_REF_CLK){slash}SSP1_SCK{slash}CLKOUT{slash}I2S0_RX_MCLK{slash}I2S1_TX_SCK-Pad68)") (class "Default")
      (node (ref "U1") (pin "68") (pinfunction "P1_19/ENET_TX_CLK(ENET_REF_CLK)/SSP1_SCK/CLKOUT/I2S0_RX_MCLK/I2S1_TX_SCK_68") (pintype "bidirectional+no_connect"))
    )
    (net (code "139") (name "unconnected-(U1A-P1_20{slash}GPIO0[15]{slash}SSP1_SSEL{slash}ENET_TXD1{slash}T0_CAP2{slash}SGPIO13-Pad70)") (class "Default")
      (node (ref "U1") (pin "70") (pinfunction "P1_20/GPIO0[15]/SSP1_SSEL/ENET_TXD1/T0_CAP2/SGPIO13_70") (pintype "bidirectional+no_connect"))
    )
    (net (code "140") (name "unconnected-(U1A-P2_6{slash}SGPIO7{slash}U0_DIR{slash}EMC_A10{slash}USB0_IND0{slash}GPIO5[6]{slash}CTIN_7{slash}T3_CAP3-Pad95)") (class "Default")
      (node (ref "U1") (pin "95") (pinfunction "P2_6/SGPIO7/U0_DIR/EMC_A10/USB0_IND0/GPIO5[6]/CTIN_7/T3_CAP3_95") (pintype "bidirectional"))
    )
    (net (code "141") (name "unconnected-(U1A-P2_10{slash}GPIO0[14]{slash}CTOUT_2{slash}U2_TXD{slash}EMC_A1-Pad104)") (class "Default")
      (node (ref "U1") (pin "104") (pinfunction "P2_10/GPIO0[14]/CTOUT_2/U2_TXD/EMC_A1_104") (pintype "bidirectional"))
    )
    (net (code "142") (name "unconnected-(U1A-P2_11{slash}GPIO1[11]{slash}CTOUT_5{slash}U2_RXD{slash}EMC_A2-Pad105)") (class "Default")
      (node (ref "U1") (pin "105") (pinfunction "P2_11/GPIO1[11]/CTOUT_5/U2_RXD/EMC_A2_105") (pintype "bidirectional"))
    )
    (net (code "143") (name "unconnected-(U1A-P2_12{slash}GPIO1[12]{slash}CTOUT_4{slash}EMC_A3{slash}U2_UCLK-Pad106)") (class "Default")
      (node (ref "U1") (pin "106") (pinfunction "P2_12/GPIO1[12]/CTOUT_4/EMC_A3/U2_UCLK_106") (pintype "bidirectional"))
    )
    (net (code "144") (name "unconnected-(U1A-P2_13{slash}GPIO1[13]{slash}CTIN_4{slash}EMC_A4{slash}U2_DIR-Pad108)") (class "Default")
      (node (ref "U1") (pin "108") (pinfunction "P2_13/GPIO1[13]/CTIN_4/EMC_A4/U2_DIR_108") (pintype "bidirectional"))
    )
    (net (code "145") (name "unconnected-(U1A-P3_3{slash}SPI_SCK{slash}SSP0_SCK{slash}SPIFI_SCK{slash}CGU_OUT1{slash}I2S0_TX_MCLK{slash}I2S1_TX_SCK-Pad118)") (class "Default")
      (node (ref "U1") (pin "118") (pinfunction "P3_3/SPI_SCK/SSP0_SCK/SPIFI_SCK/CGU_OUT1/I2S0_TX_MCLK/I2S1_TX_SCK_118") (pintype "bidirectional+no_connect"))
    )
    (net (code "146") (name "unconnected-(U1A-P3_7{slash}SPI_MOSI{slash}SSP0_MISO{slash}SPIFI_MOSI{slash}GPIO5[10]{slash}SSP0_MOSI-Pad123)") (class "Default")
      (node (ref "U1") (pin "123") (pinfunction "P3_7/SPI_MOSI/SSP0_MISO/SPIFI_MOSI/GPIO5[10]/SSP0_MOSI_123") (pintype "bidirectional+no_connect"))
    )
    (net (code "147") (name "unconnected-(U1A-P3_8{slash}SPI_SSEL{slash}SSP0_MOSI{slash}SPIFI_CS{slash}GPIO5[11]{slash}SSP0_SSEL-Pad124)") (class "Default")
      (node (ref "U1") (pin "124") (pinfunction "P3_8/SPI_SSEL/SSP0_MOSI/SPIFI_CS/GPIO5[11]/SSP0_SSEL_124") (pintype "bidirectional+no_connect"))
    )
    (net (code "148") (name "unconnected-(U1B-P4_1{slash}GPIO2[1]{slash}CTOUT_1{slash}U3_TXD{slash}ENET_COL{slash}ADC0_1-Pad3)") (class "Default")
      (node (ref "U1") (pin "3") (pinfunction "P4_1/GPIO2[1]/CTOUT_1/U3_TXD/ENET_COL/ADC0_1_3") (pintype "bidirectional"))
    )
    (net (code "149") (name "unconnected-(U1B-P4_6{slash}GPIO2[6]{slash}CTOUT_4{slash}SGPIO12-Pad11)") (class "Default")
      (node (ref "U1") (pin "11") (pinfunction "P4_6/GPIO2[6]/CTOUT_4/SGPIO12_11") (pintype "bidirectional"))
    )
    (net (code "150") (name "unconnected-(U1B-P4_7{slash}GP_CLKIN{slash}I2S1_TX_SCK{slash}I2S0_TX_SCK-Pad14)") (class "Default")
      (node (ref "U1") (pin "14") (pinfunction "P4_7/GP_CLKIN/I2S1_TX_SCK/I2S0_TX_SCK_14") (pintype "bidirectional"))
    )
    (net (code "151") (name "unconnected-(U1B-P5_4{slash}GPIO2[13]{slash}MCOB0{slash}EMC_D8{slash}U1_CTS{slash}T1_MAT0-Pad57)") (class "Default")
      (node (ref "U1") (pin "57") (pinfunction "P5_4/GPIO2[13]/MCOB0/EMC_D8/U1_CTS/T1_MAT0_57") (pintype "bidirectional"))
    )
    (net (code "152") (name "unconnected-(U1B-P5_5{slash}GPIO2[14]{slash}MCOA1{slash}EMC_D9{slash}U1_DCD{slash}T1_MAT1-Pad58)") (class "Default")
      (node (ref "U1") (pin "58") (pinfunction "P5_5/GPIO2[14]/MCOA1/EMC_D9/U1_DCD/T1_MAT1_58") (pintype "bidirectional"))
    )
    (net (code "153") (name "unconnected-(U1B-P5_6{slash}GPIO2[15]{slash}MCOB1{slash}EMC_D10{slash}U1_TXD{slash}T1_MAT2-Pad63)") (class "Default")
      (node (ref "U1") (pin "63") (pinfunction "P5_6/GPIO2[15]/MCOB1/EMC_D10/U1_TXD/T1_MAT2_63") (pintype "bidirectional"))
    )
    (net (code "154") (name "unconnected-(U1B-P6_0{slash}I2S0_RX_MCLK{slash}I2S0_RX_SCK-Pad73)") (class "Default")
      (node (ref "U1") (pin "73") (pinfunction "P6_0/I2S0_RX_MCLK/I2S0_RX_SCK_73") (pintype "bidirectional"))
    )
    (net (code "155") (name "unconnected-(U1B-P6_11{slash}GPIO3[7]{slash}EMC_CKEOUT0{slash}T2_MAT3-Pad101)") (class "Default")
      (node (ref "U1") (pin "101") (pinfunction "P6_11/GPIO3[7]/EMC_CKEOUT0/T2_MAT3_101") (pintype "bidirectional"))
    )
    (net (code "156") (name "unconnected-(U1B-P6_12{slash}GPIO2[8]{slash}CTOUT_7{slash}EMC_DQMOUT0-Pad103)") (class "Default")
      (node (ref "U1") (pin "103") (pinfunction "P6_12/GPIO2[8]/CTOUT_7/EMC_DQMOUT0_103") (pintype "bidirectional"))
    )
    (net (code "157") (name "unconnected-(U1B-P7_4{slash}GPIO3[12]{slash}CTOUT_13{slash}TRACEDATA[0]{slash}ADC0_4-Pad132)") (class "Default")
      (node (ref "U1") (pin "132") (pinfunction "P7_4/GPIO3[12]/CTOUT_13/TRACEDATA[0]/ADC0_4_132") (pintype "bidirectional"))
    )
    (net (code "158") (name "unconnected-(U1B-P7_5{slash}GPIO3[13]{slash}CTOUT_12{slash}TRACEDATA[1]{slash}ADC0_3-Pad133)") (class "Default")
      (node (ref "U1") (pin "133") (pinfunction "P7_5/GPIO3[13]/CTOUT_12/TRACEDATA[1]/ADC0_3_133") (pintype "bidirectional"))
    )
    (net (code "159") (name "unconnected-(U1B-P7_6{slash}GPIO3[14]{slash}CTOUT_11{slash}TRACEDATA[2]-Pad134)") (class "Default")
      (node (ref "U1") (pin "134") (pinfunction "P7_6/GPIO3[14]/CTOUT_11/TRACEDATA[2]_134") (pintype "bidirectional"))
    )
    (net (code "160") (name "unconnected-(U1B-P7_7{slash}GPIO3[15]{slash}CTOUT_8{slash}TRACEDATA[3]{slash}ENET_MDC{slash}SGPIO7{slash}ADC1_6-Pad140)") (class "Default")
      (node (ref "U1") (pin "140") (pinfunction "P7_7/GPIO3[15]/CTOUT_8/TRACEDATA[3]/ENET_MDC/SGPIO7/ADC1_6_140") (pintype "bidirectional"))
    )
    (net (code "161") (name "unconnected-(U1B-PF_4{slash}SSP1_SCK{slash}GP_CLKIN{slash}TRACECLK{slash}I2S0_TX_MCLK{slash}I2S0_RX_SCK-Pad120)") (class "Default")
      (node (ref "U1") (pin "120") (pinfunction "PF_4/SSP1_SCK/GP_CLKIN/TRACECLK/I2S0_TX_MCLK/I2S0_RX_SCK_120") (pintype "bidirectional"))
    )
    (net (code "162") (name "unconnected-(U1C-CLK2{slash}EMC_CLK3{slash}CLKOUT{slash}SD_CLK{slash}EMC_CLK23{slash}I2S0_TX_MCLK{slash}I2S1_RX_SCK-Pad99)") (class "Default")
      (node (ref "U1") (pin "99") (pinfunction "CLK2/EMC_CLK3/CLKOUT/SD_CLK/EMC_CLK23/I2S0_TX_MCLK/I2S1_RX_SCK_99") (pintype "bidirectional+no_connect"))
    )
    (net (code "163") (name "unconnected-(U1D-I2C0_SCL-Pad92)") (class "Default")
      (node (ref "U1") (pin "92") (pinfunction "I2C0_SCL_92") (pintype "bidirectional"))
    )
    (net (code "164") (name "unconnected-(U1D-I2C0_SDA-Pad93)") (class "Default")
      (node (ref "U1") (pin "93") (pinfunction "I2C0_SDA_93") (pintype "bidirectional"))
    )
    (net (code "165") (name "unconnected-(U1D-RTC_ALARM-Pad129)") (class "Default")
      (node (ref "U1") (pin "129") (pinfunction "RTC_ALARM_129") (pintype "output+no_connect"))
    )
    (net (code "166") (name "unconnected-(U1D-WAKEUP0-Pad130)") (class "Default")
      (node (ref "U1") (pin "130") (pinfunction "WAKEUP0_130") (pintype "input+no_connect"))
    )
    (net (code "167") (name "unconnected-(U2-NC-Pad6)") (class "Default")
      (node (ref "U2") (pin "6") (pinfunction "NC_6") (pintype "passive"))
    )
    (net (code "168") (name "unconnected-(U2-NC-Pad9)") (class "Default")
      (node (ref "U2") (pin "9") (pinfunction "NC_9") (pintype "passive"))
    )
  )
)
